# OpenPLCv0_2_0_TopLevel.net
KiCad netlist of a schematic drawn in Altium Designer
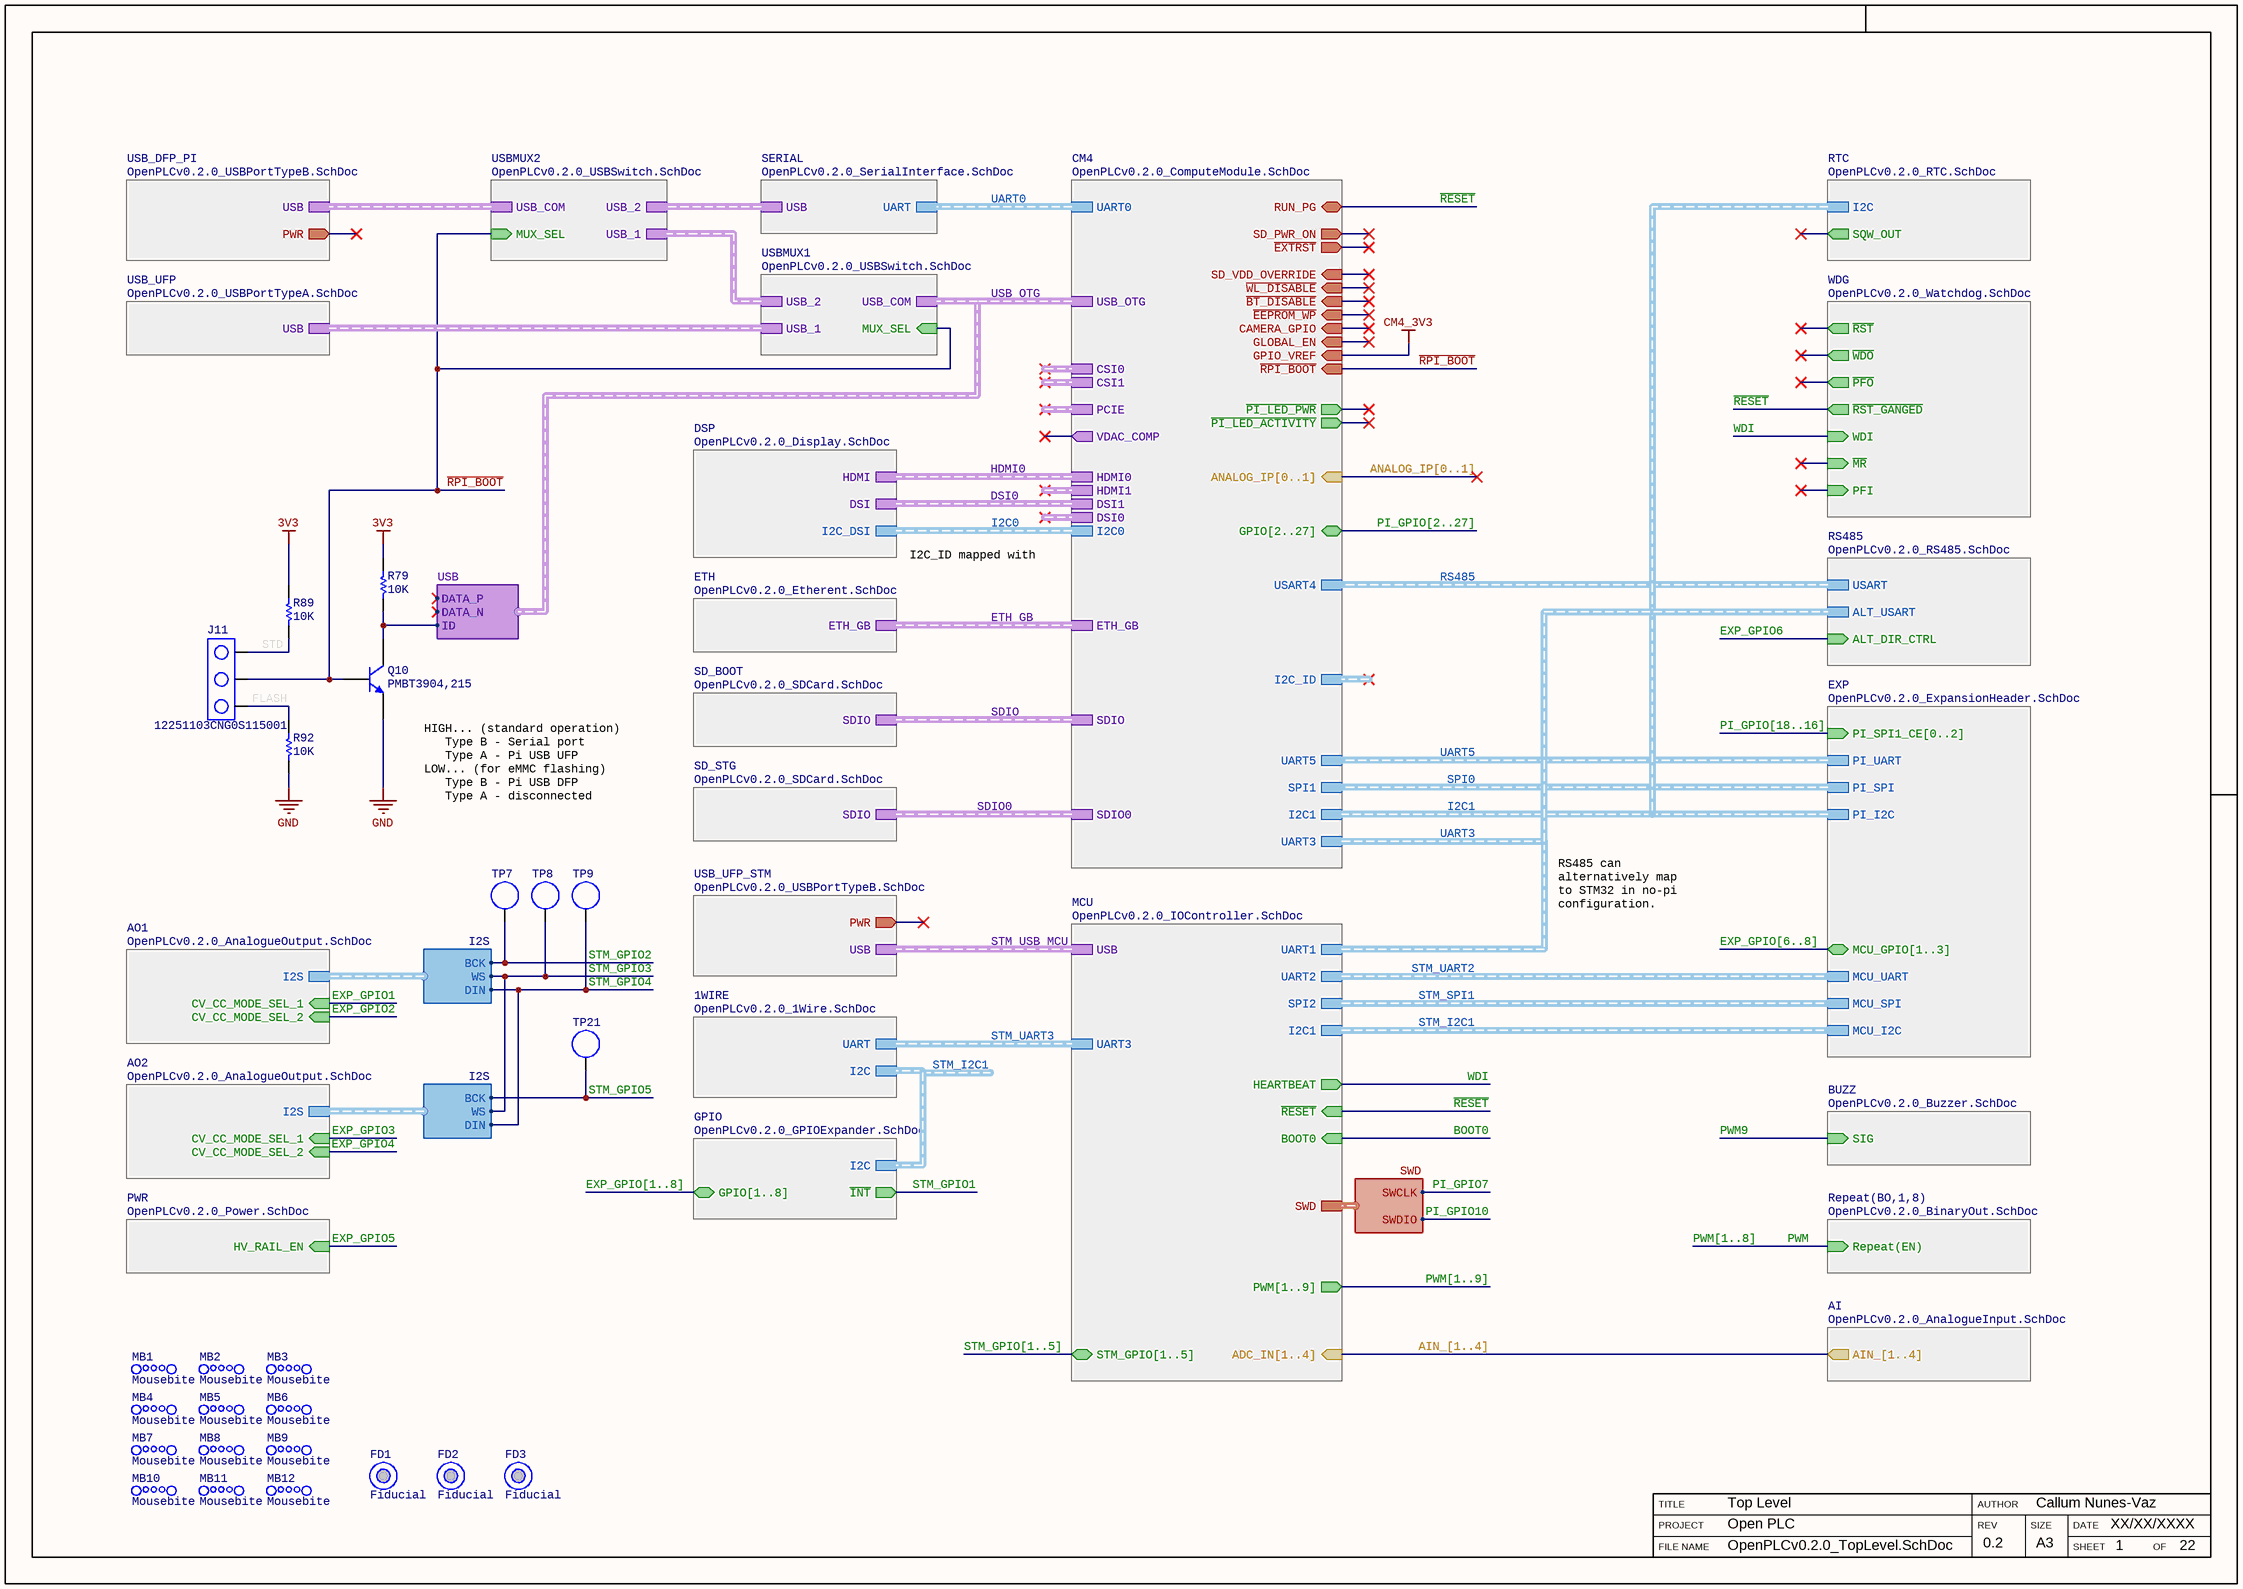
[diagram p0: OpenPLCv0.2.0_TopLevel.SchDoc]

(export (version "E")
  (design (tool "Eeschema 10.0.6"))
  (components
    (comp (ref "FD1")
      (value "Fiducial")
      (footprint "Fiducial")
      (libsource (lib "OpenPLCv0.2.0_Misc") (part "Fiducial"))
    )
    (comp (ref "FD2")
      (value "Fiducial")
      (footprint "Fiducial")
      (libsource (lib "OpenPLCv0.2.0_Misc") (part "Fiducial"))
    )
    (comp (ref "FD3")
      (value "Fiducial")
      (footprint "Fiducial")
      (libsource (lib "OpenPLCv0.2.0_Misc") (part "Fiducial"))
    )
    (comp (ref "J11")
      (value "12251103CNG0S115001")
      (footprint "Header_3POS")
      (description "Pin Header 3 1 right-angle，180degrees 2.54mm Through Hole,P=2.54mm Pin Header & Female Header RoHS")
      (libsource (lib "BrauV2_Connector") (part "3-way Jumper"))
    )
    (comp (ref "MB1")
      (value "Mousebite")
      (footprint "MOUSEBITE")
      (libsource (lib "OpenPLCv0.2.0_Misc") (part "Mousebite"))
    )
    (comp (ref "MB2")
      (value "Mousebite")
      (footprint "MOUSEBITE")
      (libsource (lib "OpenPLCv0.2.0_Misc") (part "Mousebite"))
    )
    (comp (ref "MB3")
      (value "Mousebite")
      (footprint "MOUSEBITE")
      (libsource (lib "OpenPLCv0.2.0_Misc") (part "Mousebite"))
    )
    (comp (ref "MB4")
      (value "Mousebite")
      (footprint "MOUSEBITE")
      (libsource (lib "OpenPLCv0.2.0_Misc") (part "Mousebite"))
    )
    (comp (ref "MB5")
      (value "Mousebite")
      (footprint "MOUSEBITE")
      (libsource (lib "OpenPLCv0.2.0_Misc") (part "Mousebite"))
    )
    (comp (ref "MB6")
      (value "Mousebite")
      (footprint "MOUSEBITE")
      (libsource (lib "OpenPLCv0.2.0_Misc") (part "Mousebite"))
    )
    (comp (ref "MB7")
      (value "Mousebite")
      (footprint "MOUSEBITE")
      (libsource (lib "OpenPLCv0.2.0_Misc") (part "Mousebite"))
    )
    (comp (ref "MB8")
      (value "Mousebite")
      (footprint "MOUSEBITE")
      (libsource (lib "OpenPLCv0.2.0_Misc") (part "Mousebite"))
    )
    (comp (ref "MB9")
      (value "Mousebite")
      (footprint "MOUSEBITE")
      (libsource (lib "OpenPLCv0.2.0_Misc") (part "Mousebite"))
    )
    (comp (ref "MB10")
      (value "Mousebite")
      (footprint "MOUSEBITE")
      (libsource (lib "OpenPLCv0.2.0_Misc") (part "Mousebite"))
    )
    (comp (ref "MB11")
      (value "Mousebite")
      (footprint "MOUSEBITE")
      (libsource (lib "OpenPLCv0.2.0_Misc") (part "Mousebite"))
    )
    (comp (ref "MB12")
      (value "Mousebite")
      (footprint "MOUSEBITE")
      (libsource (lib "OpenPLCv0.2.0_Misc") (part "Mousebite"))
    )
    (comp (ref "Q10")
      (value "PMBT3904,215")
      (footprint "SOT23-3")
      (description "NPN 200mA 40V 250mW SOT-23(SOT-23-3) Transistors (NPN/PNP) RoHS")
      (libsource (lib "BrauV2_Transistor") (part "PMBT3904,215"))
    )
    (comp (ref "R79")
      (value "RC0402FR-0710KL")
      (footprint "SMD_RES_0402(1005)_N")
      (description "10kΩ ±1% 1/16W ±100ppm/℃ 0402 Chip Resistor - Surface Mount RoHS")
      (fields (field (name "TOLERANCE") "1%") (field (name "RESISTANCE") "10K"))
      (libsource (lib "BrauV2_Resistor") (part "10K 0402 1% 1/16W"))
    )
    (comp (ref "R89")
      (value "RC0402FR-0710KL")
      (footprint "SMD_RES_0402(1005)_N")
      (description "10kΩ ±1% 1/16W ±100ppm/℃ 0402 Chip Resistor - Surface Mount RoHS")
      (fields (field (name "TOLERANCE") "1%") (field (name "RESISTANCE") "10K"))
      (libsource (lib "BrauV2_Resistor") (part "10K 0402 1% 1/16W"))
    )
    (comp (ref "R92")
      (value "RC0402FR-0710KL")
      (footprint "SMD_RES_0402(1005)_N")
      (description "10kΩ ±1% 1/16W ±100ppm/℃ 0402 Chip Resistor - Surface Mount RoHS")
      (fields (field (name "TOLERANCE") "1%") (field (name "RESISTANCE") "10K"))
      (libsource (lib "BrauV2_Resistor") (part "10K 0402 1% 1/16W"))
    )
    (comp (ref "TP7")
      (value "TestPoint")
      (footprint "Pad")
      (libsource (lib "OpenPLCv0.2.0_Misc") (part "Test point"))
    )
    (comp (ref "TP8")
      (value "TestPoint")
      (footprint "Pad")
      (libsource (lib "OpenPLCv0.2.0_Misc") (part "Test point"))
    )
    (comp (ref "TP9")
      (value "TestPoint")
      (footprint "Pad")
      (libsource (lib "OpenPLCv0.2.0_Misc") (part "Test point"))
    )
    (comp (ref "TP21")
      (value "TestPoint")
      (footprint "Pad")
      (libsource (lib "OpenPLCv0.2.0_Misc") (part "Test point"))
    )
  )
  (nets
    (net (code "76") (name "/FLASH") (class "Default")
      (node (ref "J11") (pin "3") (pinfunction "3_3") (pintype "passive"))
      (node (ref "R92") (pin "2") (pinfunction "2_2") (pintype "passive"))
    )
    (net (code "95") (name "/STD") (class "Default")
      (node (ref "J11") (pin "1") (pinfunction "1_1") (pintype "passive"))
      (node (ref "R89") (pin "1") (pinfunction "1_1") (pintype "passive"))
    )
    (net (code "97") (name "/STM_GPIO2") (class "Default")
      (node (ref "TP7") (pin "1") (pinfunction "1_1") (pintype "passive"))
    )
    (net (code "98") (name "/STM_GPIO3") (class "Default")
      (node (ref "TP8") (pin "1") (pinfunction "1_1") (pintype "passive"))
    )
    (net (code "99") (name "/STM_GPIO4") (class "Default")
      (node (ref "TP9") (pin "1") (pinfunction "1_1") (pintype "passive"))
    )
    (net (code "100") (name "/STM_GPIO5") (class "Default")
      (node (ref "TP21") (pin "1") (pinfunction "1_1") (pintype "passive"))
    )
    (net (code "136") (name "/~{RPI_BOOT}") (class "Default")
      (node (ref "J11") (pin "2") (pinfunction "2_2") (pintype "passive"))
      (node (ref "Q10") (pin "1") (pinfunction "B_1") (pintype "passive"))
    )
    (net (code "140") (name "3V3") (class "Default")
      (node (ref "R79") (pin "1") (pinfunction "1_1") (pintype "passive"))
      (node (ref "R89") (pin "2") (pinfunction "2_2") (pintype "passive"))
    )
    (net (code "142") (name "GND") (class "Default")
      (node (ref "Q10") (pin "2") (pinfunction "E_2") (pintype "passive"))
      (node (ref "R92") (pin "1") (pinfunction "1_1") (pintype "passive"))
    )
    (net (code "143") (name "Net-(Q10-C)") (class "Default")
      (node (ref "Q10") (pin "3") (pinfunction "C_3") (pintype "passive"))
      (node (ref "R79") (pin "2") (pinfunction "2_2") (pintype "passive"))
    )
  )
)
